# Navigator_Core.net
KiCad netlist of a schematic drawn in Altium Designer
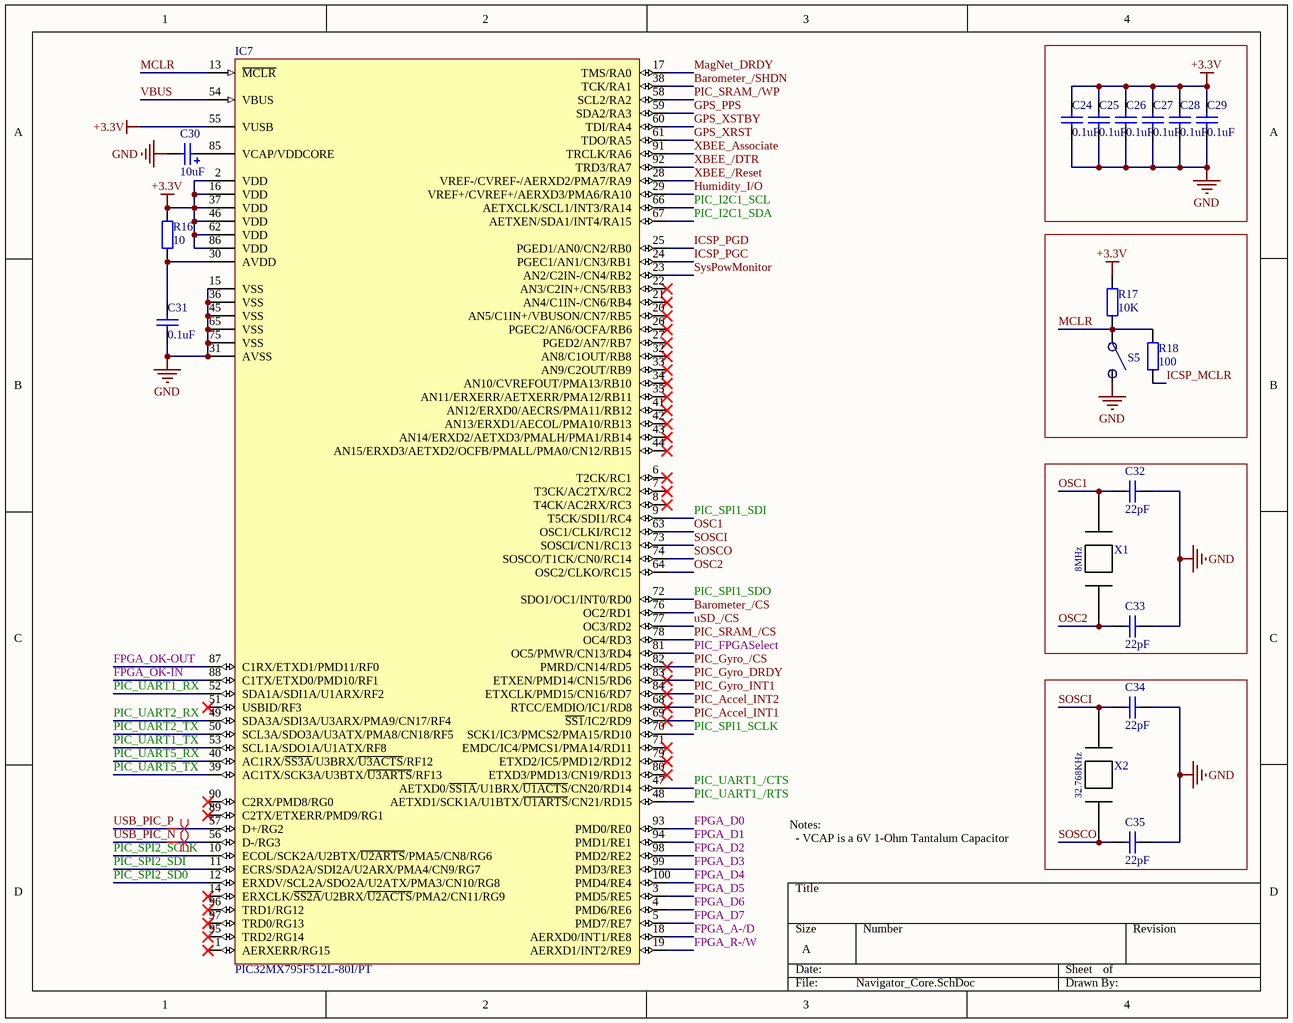
[diagram p0: Navigator_Core.SchDoc]

(export (version "E")
  (design (tool "Eeschema 10.0.6"))
  (components
    (comp (ref "C24")
      (value "0.1uF")
      (footprint "SMD 1206")
      (description "Capacitor")
      (fields (field (name "Comment") "0.1uF SMD 1206"))
      (libsource (lib "Miscellaneous Devices") (part "Cap"))
    )
    (comp (ref "C25")
      (value "0.1uF")
      (footprint "SMD 1206")
      (description "Capacitor")
      (fields (field (name "Comment") "0.1uF SMD 1206"))
      (libsource (lib "Miscellaneous Devices") (part "Cap"))
    )
    (comp (ref "C26")
      (value "0.1uF")
      (footprint "SMD 1206")
      (description "Capacitor")
      (fields (field (name "Comment") "0.1uF SMD 1206"))
      (libsource (lib "Miscellaneous Devices") (part "Cap"))
    )
    (comp (ref "C27")
      (value "0.1uF")
      (footprint "SMD 1206")
      (description "Capacitor")
      (fields (field (name "Comment") "0.1uF SMD 1206"))
      (libsource (lib "Miscellaneous Devices") (part "Cap"))
    )
    (comp (ref "C28")
      (value "0.1uF")
      (footprint "SMD 1206")
      (description "Capacitor")
      (fields (field (name "Comment") "0.1uF SMD 1206"))
      (libsource (lib "Miscellaneous Devices") (part "Cap"))
    )
    (comp (ref "C29")
      (value "0.1uF")
      (footprint "SMD 1206")
      (description "Capacitor")
      (fields (field (name "Comment") "0.1uF SMD 1206"))
      (libsource (lib "Miscellaneous Devices") (part "Cap"))
    )
    (comp (ref "C30")
      (value "10uF")
      (footprint "Capacitor - Tantalum Case A")
      (description "Tantalum Capacitor - Case A")
      (fields (field (name "Comment") "10uF Low-ESR Tantalum CaseA"))
      (libsource (lib "Ad-Flier_Parts") (part "SMD_Cap_Tantalum"))
    )
    (comp (ref "C31")
      (value "0.1uF")
      (footprint "SMD 1206")
      (description "Capacitor")
      (fields (field (name "Comment") "0.1uF SMD 1206"))
      (libsource (lib "Miscellaneous Devices") (part "Cap"))
    )
    (comp (ref "C32")
      (value "22pF")
      (footprint "SMD 1206")
      (description "Capacitor")
      (fields (field (name "Comment") "22pF SMD 1206"))
      (libsource (lib "Miscellaneous Devices") (part "Cap"))
    )
    (comp (ref "C33")
      (value "22pF")
      (footprint "SMD 1206")
      (description "Capacitor")
      (fields (field (name "Comment") "22pF SMD 1206"))
      (libsource (lib "Miscellaneous Devices") (part "Cap"))
    )
    (comp (ref "C34")
      (value "22pF")
      (footprint "SMD 1206")
      (description "Capacitor")
      (fields (field (name "Comment") "22pF SMD 1206"))
      (libsource (lib "Miscellaneous Devices") (part "Cap"))
    )
    (comp (ref "C35")
      (value "22pF")
      (footprint "SMD 1206")
      (description "Capacitor")
      (fields (field (name "Comment") "22pF SMD 1206"))
      (libsource (lib "Miscellaneous Devices") (part "Cap"))
    )
    (comp (ref "IC7")
      (value "PIC32MX795F512L-80I/PT")
      (footprint "TQFP-PF100_L")
      (fields (field (name "PUBLISHER") "Altium Limited"))
      (libsource (lib "Microchip Microcontroller 32-Bit PIC32") (part "PIC32MX795F512L-80I/PT"))
    )
    (comp (ref "R16")
      (value "10")
      (footprint "SMD 0805")
      (description "Resistor")
      (fields (field (name "Comment") "10 SMD 0805"))
      (libsource (lib "") (part "Res2_1"))
    )
    (comp (ref "R17")
      (value "10K")
      (footprint "SMD 0805")
      (description "Resistor")
      (fields (field (name "Comment") "10K SMD 0805"))
      (libsource (lib "") (part "Res2_1"))
    )
    (comp (ref "R18")
      (value "100")
      (footprint "SMD 0805")
      (description "Resistor")
      (fields (field (name "Comment") "100 SMD 0805"))
      (libsource (lib "Miscellaneous Devices") (part "Res2"))
    )
    (comp (ref "S5")
      (value "SMD Tactile Switch")
      (footprint "SMD Tactile Switch")
      (libsource (lib "Ad-Flier_Parts") (part "SMD Tactile Switch"))
    )
    (comp (ref "X1")
      (value "XT9M20ANA8M")
      (footprint "XT9M20ANA8M - 8MHz Capacitor")
      (description "8MHz SMD Crystal")
      (libsource (lib "Ad-Flier_Parts") (part "XT9M20ANA8M"))
    )
    (comp (ref "X2")
      (value "SSP-T6-7PF-20PPM")
      (footprint "32.768KHz Crystal")
      (description "32.768KHz 7pF SMD Crystal")
      (libsource (lib "Ad-Flier_Parts") (part "SSP-T6-7PF-20PPM"))
    )
  )
  (nets
    (net (code "1") (name "+3.3V") (class "Default")
      (node (ref "C24") (pin "1") (pinfunction "1_1") (pintype "passive"))
      (node (ref "C25") (pin "1") (pinfunction "1_1") (pintype "passive"))
      (node (ref "C26") (pin "1") (pinfunction "1_1") (pintype "passive"))
      (node (ref "C27") (pin "1") (pinfunction "1_1") (pintype "passive"))
      (node (ref "C28") (pin "1") (pinfunction "1_1") (pintype "passive"))
      (node (ref "C29") (pin "1") (pinfunction "1_1") (pintype "passive"))
      (node (ref "IC7") (pin "16") (pinfunction "VDD_16") (pintype "power_in"))
      (node (ref "IC7") (pin "2") (pinfunction "VDD_2") (pintype "power_in"))
      (node (ref "IC7") (pin "37") (pinfunction "VDD_37") (pintype "power_in"))
      (node (ref "IC7") (pin "46") (pinfunction "VDD_46") (pintype "power_in"))
      (node (ref "IC7") (pin "55") (pinfunction "VUSB_55") (pintype "power_in"))
      (node (ref "IC7") (pin "62") (pinfunction "VDD_62") (pintype "power_in"))
      (node (ref "IC7") (pin "86") (pinfunction "VDD_86") (pintype "power_in"))
      (node (ref "R16") (pin "2") (pinfunction "2_2") (pintype "passive"))
      (node (ref "R17") (pin "2") (pinfunction "2_2") (pintype "passive"))
    )
    (net (code "2") (name "/Barometer_{slash}CS") (class "Default")
      (node (ref "IC7") (pin "76") (pinfunction "OC2/RD1_76") (pintype "bidirectional"))
    )
    (net (code "3") (name "/Barometer_{slash}SHDN") (class "Default")
      (node (ref "IC7") (pin "38") (pinfunction "TCK/RA1_38") (pintype "bidirectional"))
    )
    (net (code "4") (name "/FPGA_A-{slash}D") (class "Default")
      (node (ref "IC7") (pin "18") (pinfunction "AERXD0/INT1/RE8_18") (pintype "bidirectional"))
    )
    (net (code "5") (name "/FPGA_D0") (class "Default")
      (node (ref "IC7") (pin "93") (pinfunction "PMD0/RE0_93") (pintype "bidirectional"))
    )
    (net (code "6") (name "/FPGA_D1") (class "Default")
      (node (ref "IC7") (pin "94") (pinfunction "PMD1/RE1_94") (pintype "bidirectional"))
    )
    (net (code "7") (name "/FPGA_D2") (class "Default")
      (node (ref "IC7") (pin "98") (pinfunction "PMD2/RE2_98") (pintype "bidirectional"))
    )
    (net (code "8") (name "/FPGA_D3") (class "Default")
      (node (ref "IC7") (pin "99") (pinfunction "PMD3/RE3_99") (pintype "bidirectional"))
    )
    (net (code "9") (name "/FPGA_D4") (class "Default")
      (node (ref "IC7") (pin "100") (pinfunction "PMD4/RE4_100") (pintype "bidirectional"))
    )
    (net (code "10") (name "/FPGA_D5") (class "Default")
      (node (ref "IC7") (pin "3") (pinfunction "PMD5/RE5_3") (pintype "bidirectional"))
    )
    (net (code "11") (name "/FPGA_D6") (class "Default")
      (node (ref "IC7") (pin "4") (pinfunction "PMD6/RE6_4") (pintype "bidirectional"))
    )
    (net (code "12") (name "/FPGA_D7") (class "Default")
      (node (ref "IC7") (pin "5") (pinfunction "PMD7/RE7_5") (pintype "bidirectional"))
    )
    (net (code "13") (name "/FPGA_OK-IN") (class "Default")
      (node (ref "IC7") (pin "88") (pinfunction "C1TX/ETXD0/PMD10/RF1_88") (pintype "bidirectional"))
    )
    (net (code "14") (name "/FPGA_OK-OUT") (class "Default")
      (node (ref "IC7") (pin "87") (pinfunction "C1RX/ETXD1/PMD11/RF0_87") (pintype "bidirectional"))
    )
    (net (code "15") (name "/FPGA_R-{slash}W") (class "Default")
      (node (ref "IC7") (pin "19") (pinfunction "AERXD1/INT2/RE9_19") (pintype "bidirectional"))
    )
    (net (code "16") (name "/GPS_PPS") (class "Default")
      (node (ref "IC7") (pin "59") (pinfunction "SDA2/RA3_59") (pintype "bidirectional"))
    )
    (net (code "17") (name "/GPS_XRST") (class "Default")
      (node (ref "IC7") (pin "61") (pinfunction "TDO/RA5_61") (pintype "bidirectional"))
    )
    (net (code "18") (name "/GPS_XSTBY") (class "Default")
      (node (ref "IC7") (pin "60") (pinfunction "TDI/RA4_60") (pintype "bidirectional"))
    )
    (net (code "19") (name "/Humidity_I{slash}O") (class "Default")
      (node (ref "IC7") (pin "29") (pinfunction "VREF+/CVREF+/AERXD3/PMA6/RA10_29") (pintype "bidirectional"))
    )
    (net (code "20") (name "/ICSP_MCLR") (class "Default")
      (node (ref "R18") (pin "2") (pinfunction "2_2") (pintype "passive"))
    )
    (net (code "21") (name "/ICSP_PGC") (class "Default")
      (node (ref "IC7") (pin "24") (pinfunction "PGEC1/AN1/CN3/RB1_24") (pintype "bidirectional"))
    )
    (net (code "22") (name "/ICSP_PGD") (class "Default")
      (node (ref "IC7") (pin "25") (pinfunction "PGED1/AN0/CN2/RB0_25") (pintype "bidirectional"))
    )
    (net (code "23") (name "/MCLR") (class "Default")
      (node (ref "IC7") (pin "13") (pinfunction "~{MCLR}_13") (pintype "input"))
      (node (ref "R17") (pin "1") (pinfunction "1_1") (pintype "passive"))
      (node (ref "R18") (pin "1") (pinfunction "1_1") (pintype "passive"))
      (node (ref "S5") (pin "2") (pintype "passive"))
    )
    (net (code "24") (name "/MagNet_DRDY") (class "Default")
      (node (ref "IC7") (pin "17") (pinfunction "TMS/RA0_17") (pintype "bidirectional"))
    )
    (net (code "25") (name "/OSC1") (class "Default")
      (node (ref "C32") (pin "2") (pinfunction "2_2") (pintype "passive"))
      (node (ref "IC7") (pin "63") (pinfunction "OSC1/CLKI/RC12_63") (pintype "bidirectional"))
      (node (ref "X1") (pin "1") (pinfunction "0_1") (pintype "passive"))
    )
    (net (code "26") (name "/OSC2") (class "Default")
      (node (ref "C33") (pin "2") (pinfunction "2_2") (pintype "passive"))
      (node (ref "IC7") (pin "64") (pinfunction "OSC2/CLKO/RC15_64") (pintype "bidirectional"))
      (node (ref "X1") (pin "0") (pinfunction "0_0") (pintype "passive"))
    )
    (net (code "27") (name "/PIC_Accel_INT1") (class "Default")
      (node (ref "IC7") (pin "69") (pinfunction "~{SS1}/IC2/RD9_69") (pintype "bidirectional+no_connect"))
    )
    (net (code "28") (name "/PIC_Accel_INT2") (class "Default")
      (node (ref "IC7") (pin "68") (pinfunction "RTCC/EMDIO/IC1/RD8_68") (pintype "bidirectional+no_connect"))
    )
    (net (code "29") (name "/PIC_FPGASelect") (class "Default")
      (node (ref "IC7") (pin "81") (pinfunction "OC5/PMWR/CN13/RD4_81") (pintype "bidirectional"))
    )
    (net (code "30") (name "/PIC_Gyro_DRDY") (class "Default")
      (node (ref "IC7") (pin "83") (pinfunction "ETXEN/PMD14/CN15/RD6_83") (pintype "bidirectional+no_connect"))
    )
    (net (code "31") (name "/PIC_Gyro_INT1") (class "Default")
      (node (ref "IC7") (pin "84") (pinfunction "ETXCLK/PMD15/CN16/RD7_84") (pintype "bidirectional+no_connect"))
    )
    (net (code "32") (name "/PIC_Gyro_{slash}CS") (class "Default")
      (node (ref "IC7") (pin "82") (pinfunction "PMRD/CN14/RD5_82") (pintype "bidirectional+no_connect"))
    )
    (net (code "33") (name "/PIC_I2C1_SCL") (class "Default")
      (node (ref "IC7") (pin "66") (pinfunction "AETXCLK/SCL1/INT3/RA14_66") (pintype "bidirectional"))
    )
    (net (code "34") (name "/PIC_I2C1_SDA") (class "Default")
      (node (ref "IC7") (pin "67") (pinfunction "AETXEN/SDA1/INT4/RA15_67") (pintype "bidirectional"))
    )
    (net (code "35") (name "/PIC_SPI1_SCLK") (class "Default")
      (node (ref "IC7") (pin "70") (pinfunction "SCK1/IC3/PMCS2/PMA15/RD10_70") (pintype "bidirectional"))
    )
    (net (code "36") (name "/PIC_SPI1_SDI") (class "Default")
      (node (ref "IC7") (pin "9") (pinfunction "T5CK/SDI1/RC4_9") (pintype "bidirectional"))
    )
    (net (code "37") (name "/PIC_SPI1_SDO") (class "Default")
      (node (ref "IC7") (pin "72") (pinfunction "SDO1/OC1/INT0/RD0_72") (pintype "bidirectional"))
    )
    (net (code "38") (name "/PIC_SPI2_SCLK") (class "Default")
      (node (ref "IC7") (pin "10") (pinfunction "ECOL/SCK2A/U2BTX/~{U2ARTS}/PMA5/CN8/RG6_10") (pintype "bidirectional"))
    )
    (net (code "39") (name "/PIC_SPI2_SD0") (class "Default")
      (node (ref "IC7") (pin "12") (pinfunction "ERXDV/SCL2A/SDO2A/U2ATX/PMA3/CN10/RG8_12") (pintype "bidirectional"))
    )
    (net (code "40") (name "/PIC_SPI2_SDI") (class "Default")
      (node (ref "IC7") (pin "11") (pinfunction "ECRS/SDA2A/SDI2A/U2ARX/PMA4/CN9/RG7_11") (pintype "bidirectional"))
    )
    (net (code "41") (name "/PIC_SRAM_{slash}CS") (class "Default")
      (node (ref "IC7") (pin "78") (pinfunction "OC4/RD3_78") (pintype "bidirectional"))
    )
    (net (code "42") (name "/PIC_SRAM_{slash}WP") (class "Default")
      (node (ref "IC7") (pin "58") (pinfunction "SCL2/RA2_58") (pintype "bidirectional"))
    )
    (net (code "43") (name "/PIC_UART1_RX") (class "Default")
      (node (ref "IC7") (pin "52") (pinfunction "SDA1A/SDI1A/U1ARX/RF2_52") (pintype "bidirectional"))
    )
    (net (code "44") (name "/PIC_UART1_TX") (class "Default")
      (node (ref "IC7") (pin "53") (pinfunction "SCL1A/SDO1A/U1ATX/RF8_53") (pintype "bidirectional"))
    )
    (net (code "45") (name "/PIC_UART1_{slash}CTS") (class "Default")
      (node (ref "IC7") (pin "47") (pinfunction "AETXD0/~{SS1A}/U1BRX/~{U1ACTS}/CN20/RD14_47") (pintype "bidirectional"))
    )
    (net (code "46") (name "/PIC_UART1_{slash}RTS") (class "Default")
      (node (ref "IC7") (pin "48") (pinfunction "AETXD1/SCK1A/U1BTX/~{U1ARTS}/CN21/RD15_48") (pintype "bidirectional"))
    )
    (net (code "47") (name "/PIC_UART2_RX") (class "Default")
      (node (ref "IC7") (pin "49") (pinfunction "SDA3A/SDI3A/U3ARX/PMA9/CN17/RF4_49") (pintype "bidirectional"))
    )
    (net (code "48") (name "/PIC_UART2_TX") (class "Default")
      (node (ref "IC7") (pin "50") (pinfunction "SCL3A/SDO3A/U3ATX/PMA8/CN18/RF5_50") (pintype "bidirectional"))
    )
    (net (code "49") (name "/PIC_UART5_RX") (class "Default")
      (node (ref "IC7") (pin "40") (pinfunction "AC1RX/~{SS3A}/U3BRX/~{U3ACTS}/RF12_40") (pintype "bidirectional"))
    )
    (net (code "50") (name "/PIC_UART5_TX") (class "Default")
      (node (ref "IC7") (pin "39") (pinfunction "AC1TX/SCK3A/U3BTX/~{U3ARTS}/RF13_39") (pintype "bidirectional"))
    )
    (net (code "51") (name "/SOSCI") (class "Default")
      (node (ref "C34") (pin "2") (pinfunction "2_2") (pintype "passive"))
      (node (ref "IC7") (pin "73") (pinfunction "SOSCI/CN1/RC13_73") (pintype "bidirectional"))
      (node (ref "X2") (pin "0") (pinfunction "2_0") (pintype "passive"))
    )
    (net (code "52") (name "/SOSCO") (class "Default")
      (node (ref "C35") (pin "2") (pinfunction "2_2") (pintype "passive"))
      (node (ref "IC7") (pin "74") (pinfunction "SOSCO/T1CK/CN0/RC14_74") (pintype "bidirectional"))
      (node (ref "X2") (pin "1") (pinfunction "2_1") (pintype "passive"))
    )
    (net (code "53") (name "/SysPowMonitor") (class "Default")
      (node (ref "IC7") (pin "23") (pinfunction "AN2/C2IN-/CN4/RB2_23") (pintype "bidirectional"))
    )
    (net (code "54") (name "/USB_PIC_N") (class "Default")
      (node (ref "IC7") (pin "56") (pinfunction "D-/RG3_56") (pintype "bidirectional"))
    )
    (net (code "55") (name "/USB_PIC_P") (class "Default")
      (node (ref "IC7") (pin "57") (pinfunction "D+/RG2_57") (pintype "bidirectional"))
    )
    (net (code "56") (name "/VBUS") (class "Default")
      (node (ref "IC7") (pin "54") (pinfunction "VBUS_54") (pintype "input"))
    )
    (net (code "57") (name "/XBEE_Associate") (class "Default")
      (node (ref "IC7") (pin "91") (pinfunction "TRCLK/RA6_91") (pintype "bidirectional"))
    )
    (net (code "58") (name "/XBEE_{slash}DTR") (class "Default")
      (node (ref "IC7") (pin "92") (pinfunction "TRD3/RA7_92") (pintype "bidirectional"))
    )
    (net (code "59") (name "/XBEE_{slash}Reset") (class "Default")
      (node (ref "IC7") (pin "28") (pinfunction "VREF-/CVREF-/AERXD2/PMA7/RA9_28") (pintype "bidirectional"))
    )
    (net (code "60") (name "/uSD_{slash}CS") (class "Default")
      (node (ref "IC7") (pin "77") (pinfunction "OC3/RD2_77") (pintype "bidirectional"))
    )
    (net (code "61") (name "GND") (class "Default")
      (node (ref "C24") (pin "2") (pinfunction "2_2") (pintype "passive"))
      (node (ref "C25") (pin "2") (pinfunction "2_2") (pintype "passive"))
      (node (ref "C26") (pin "2") (pinfunction "2_2") (pintype "passive"))
      (node (ref "C27") (pin "2") (pinfunction "2_2") (pintype "passive"))
      (node (ref "C28") (pin "2") (pinfunction "2_2") (pintype "passive"))
      (node (ref "C29") (pin "2") (pinfunction "2_2") (pintype "passive"))
      (node (ref "C30") (pin "2") (pinfunction "-_2") (pintype "passive"))
      (node (ref "C31") (pin "2") (pinfunction "2_2") (pintype "passive"))
      (node (ref "C32") (pin "1") (pinfunction "1_1") (pintype "passive"))
      (node (ref "C33") (pin "1") (pinfunction "1_1") (pintype "passive"))
      (node (ref "C34") (pin "1") (pinfunction "1_1") (pintype "passive"))
      (node (ref "C35") (pin "1") (pinfunction "1_1") (pintype "passive"))
      (node (ref "IC7") (pin "15") (pinfunction "VSS_15") (pintype "power_in"))
      (node (ref "IC7") (pin "31") (pinfunction "AVSS_31") (pintype "power_in"))
      (node (ref "IC7") (pin "36") (pinfunction "VSS_36") (pintype "power_in"))
      (node (ref "IC7") (pin "45") (pinfunction "VSS_45") (pintype "power_in"))
      (node (ref "IC7") (pin "65") (pinfunction "VSS_65") (pintype "power_in"))
      (node (ref "IC7") (pin "75") (pinfunction "VSS_75") (pintype "power_in"))
      (node (ref "S5") (pin "1") (pintype "passive"))
    )
    (net (code "62") (name "Net-(C30-+)") (class "Default")
      (node (ref "C30") (pin "1") (pinfunction "+_1") (pintype "passive"))
      (node (ref "IC7") (pin "85") (pinfunction "VCAP/VDDCORE_85") (pintype "power_in"))
    )
    (net (code "63") (name "Net-(IC7-AVDD)") (class "Default")
      (node (ref "C31") (pin "1") (pinfunction "1_1") (pintype "passive"))
      (node (ref "IC7") (pin "30") (pinfunction "AVDD_30") (pintype "power_in"))
      (node (ref "R16") (pin "1") (pinfunction "1_1") (pintype "passive"))
    )
    (net (code "64") (name "unconnected-(IC7-AERXERR{slash}RG15-Pad1)") (class "Default")
      (node (ref "IC7") (pin "1") (pinfunction "AERXERR/RG15_1") (pintype "bidirectional+no_connect"))
    )
    (net (code "65") (name "unconnected-(IC7-AN3{slash}C2IN+{slash}CN5{slash}RB3-Pad22)") (class "Default")
      (node (ref "IC7") (pin "22") (pinfunction "AN3/C2IN+/CN5/RB3_22") (pintype "bidirectional+no_connect"))
    )
    (net (code "66") (name "unconnected-(IC7-AN4{slash}C1IN-{slash}CN6{slash}RB4-Pad21)") (class "Default")
      (node (ref "IC7") (pin "21") (pinfunction "AN4/C1IN-/CN6/RB4_21") (pintype "bidirectional+no_connect"))
    )
    (net (code "67") (name "unconnected-(IC7-AN5{slash}C1IN+{slash}VBUSON{slash}CN7{slash}RB5-Pad20)") (class "Default")
      (node (ref "IC7") (pin "20") (pinfunction "AN5/C1IN+/VBUSON/CN7/RB5_20") (pintype "bidirectional+no_connect"))
    )
    (net (code "68") (name "unconnected-(IC7-AN8{slash}C1OUT{slash}RB8-Pad32)") (class "Default")
      (node (ref "IC7") (pin "32") (pinfunction "AN8/C1OUT/RB8_32") (pintype "bidirectional+no_connect"))
    )
    (net (code "69") (name "unconnected-(IC7-AN9{slash}C2OUT{slash}RB9-Pad33)") (class "Default")
      (node (ref "IC7") (pin "33") (pinfunction "AN9/C2OUT/RB9_33") (pintype "bidirectional+no_connect"))
    )
    (net (code "70") (name "unconnected-(IC7-AN10{slash}CVREFOUT{slash}PMA13{slash}RB10-Pad34)") (class "Default")
      (node (ref "IC7") (pin "34") (pinfunction "AN10/CVREFOUT/PMA13/RB10_34") (pintype "bidirectional+no_connect"))
    )
    (net (code "71") (name "unconnected-(IC7-AN11{slash}ERXERR{slash}AETXERR{slash}PMA12{slash}RB11-Pad35)") (class "Default")
      (node (ref "IC7") (pin "35") (pinfunction "AN11/ERXERR/AETXERR/PMA12/RB11_35") (pintype "bidirectional+no_connect"))
    )
    (net (code "72") (name "unconnected-(IC7-AN12{slash}ERXD0{slash}AECRS{slash}PMA11{slash}RB12-Pad41)") (class "Default")
      (node (ref "IC7") (pin "41") (pinfunction "AN12/ERXD0/AECRS/PMA11/RB12_41") (pintype "bidirectional+no_connect"))
    )
    (net (code "73") (name "unconnected-(IC7-AN13{slash}ERXD1{slash}AECOL{slash}PMA10{slash}RB13-Pad42)") (class "Default")
      (node (ref "IC7") (pin "42") (pinfunction "AN13/ERXD1/AECOL/PMA10/RB13_42") (pintype "bidirectional+no_connect"))
    )
    (net (code "74") (name "unconnected-(IC7-AN14{slash}ERXD2{slash}AETXD3{slash}PMALH{slash}PMA1{slash}RB14-Pad43)") (class "Default")
      (node (ref "IC7") (pin "43") (pinfunction "AN14/ERXD2/AETXD3/PMALH/PMA1/RB14_43") (pintype "bidirectional+no_connect"))
    )
    (net (code "75") (name "unconnected-(IC7-AN15{slash}ERXD3{slash}AETXD2{slash}OCFB{slash}PMALL{slash}PMA0{slash}CN12{slash}RB15-Pad44)") (class "Default")
      (node (ref "IC7") (pin "44") (pinfunction "AN15/ERXD3/AETXD2/OCFB/PMALL/PMA0/CN12/RB15_44") (pintype "bidirectional+no_connect"))
    )
    (net (code "76") (name "unconnected-(IC7-C2RX{slash}PMD8{slash}RG0-Pad90)") (class "Default")
      (node (ref "IC7") (pin "90") (pinfunction "C2RX/PMD8/RG0_90") (pintype "bidirectional+no_connect"))
    )
    (net (code "77") (name "unconnected-(IC7-C2TX{slash}ETXERR{slash}PMD9{slash}RG1-Pad89)") (class "Default")
      (node (ref "IC7") (pin "89") (pinfunction "C2TX/ETXERR/PMD9/RG1_89") (pintype "bidirectional+no_connect"))
    )
    (net (code "78") (name "unconnected-(IC7-EMDC{slash}IC4{slash}PMCS1{slash}PMA14{slash}RD11-Pad71)") (class "Default")
      (node (ref "IC7") (pin "71") (pinfunction "EMDC/IC4/PMCS1/PMA14/RD11_71") (pintype "bidirectional+no_connect"))
    )
    (net (code "79") (name "unconnected-(IC7-ERXCLK{slash}~{SS2A}{slash}U2BRX{slash}~{U2ACTS}{slash}PMA2{slash}CN11{slash}RG9-Pad14)") (class "Default")
      (node (ref "IC7") (pin "14") (pinfunction "ERXCLK/~{SS2A}/U2BRX/~{U2ACTS}/PMA2/CN11/RG9_14") (pintype "bidirectional+no_connect"))
    )
    (net (code "80") (name "unconnected-(IC7-ETXD2{slash}IC5{slash}PMD12{slash}RD12-Pad79)") (class "Default")
      (node (ref "IC7") (pin "79") (pinfunction "ETXD2/IC5/PMD12/RD12_79") (pintype "bidirectional+no_connect"))
    )
    (net (code "81") (name "unconnected-(IC7-ETXD3{slash}PMD13{slash}CN19{slash}RD13-Pad80)") (class "Default")
      (node (ref "IC7") (pin "80") (pinfunction "ETXD3/PMD13/CN19/RD13_80") (pintype "bidirectional+no_connect"))
    )
    (net (code "82") (name "unconnected-(IC7-PGEC2{slash}AN6{slash}OCFA{slash}RB6-Pad26)") (class "Default")
      (node (ref "IC7") (pin "26") (pinfunction "PGEC2/AN6/OCFA/RB6_26") (pintype "bidirectional+no_connect"))
    )
    (net (code "83") (name "unconnected-(IC7-PGED2{slash}AN7{slash}RB7-Pad27)") (class "Default")
      (node (ref "IC7") (pin "27") (pinfunction "PGED2/AN7/RB7_27") (pintype "bidirectional+no_connect"))
    )
    (net (code "84") (name "unconnected-(IC7-T2CK{slash}RC1-Pad6)") (class "Default")
      (node (ref "IC7") (pin "6") (pinfunction "T2CK/RC1_6") (pintype "bidirectional+no_connect"))
    )
    (net (code "85") (name "unconnected-(IC7-T3CK{slash}AC2TX{slash}RC2-Pad7)") (class "Default")
      (node (ref "IC7") (pin "7") (pinfunction "T3CK/AC2TX/RC2_7") (pintype "bidirectional+no_connect"))
    )
    (net (code "86") (name "unconnected-(IC7-T4CK{slash}AC2RX{slash}RC3-Pad8)") (class "Default")
      (node (ref "IC7") (pin "8") (pinfunction "T4CK/AC2RX/RC3_8") (pintype "bidirectional+no_connect"))
    )
    (net (code "87") (name "unconnected-(IC7-TRD0{slash}RG13-Pad97)") (class "Default")
      (node (ref "IC7") (pin "97") (pinfunction "TRD0/RG13_97") (pintype "bidirectional+no_connect"))
    )
    (net (code "88") (name "unconnected-(IC7-TRD1{slash}RG12-Pad96)") (class "Default")
      (node (ref "IC7") (pin "96") (pinfunction "TRD1/RG12_96") (pintype "bidirectional+no_connect"))
    )
    (net (code "89") (name "unconnected-(IC7-TRD2{slash}RG14-Pad95)") (class "Default")
      (node (ref "IC7") (pin "95") (pinfunction "TRD2/RG14_95") (pintype "bidirectional+no_connect"))
    )
    (net (code "90") (name "unconnected-(IC7-USBID{slash}RF3-Pad51)") (class "Default")
      (node (ref "IC7") (pin "51") (pinfunction "USBID/RF3_51") (pintype "bidirectional+no_connect"))
    )
  )
)
